# rls_slide_expand_01.net
KiCad netlist of a schematic drawn in EAGLE
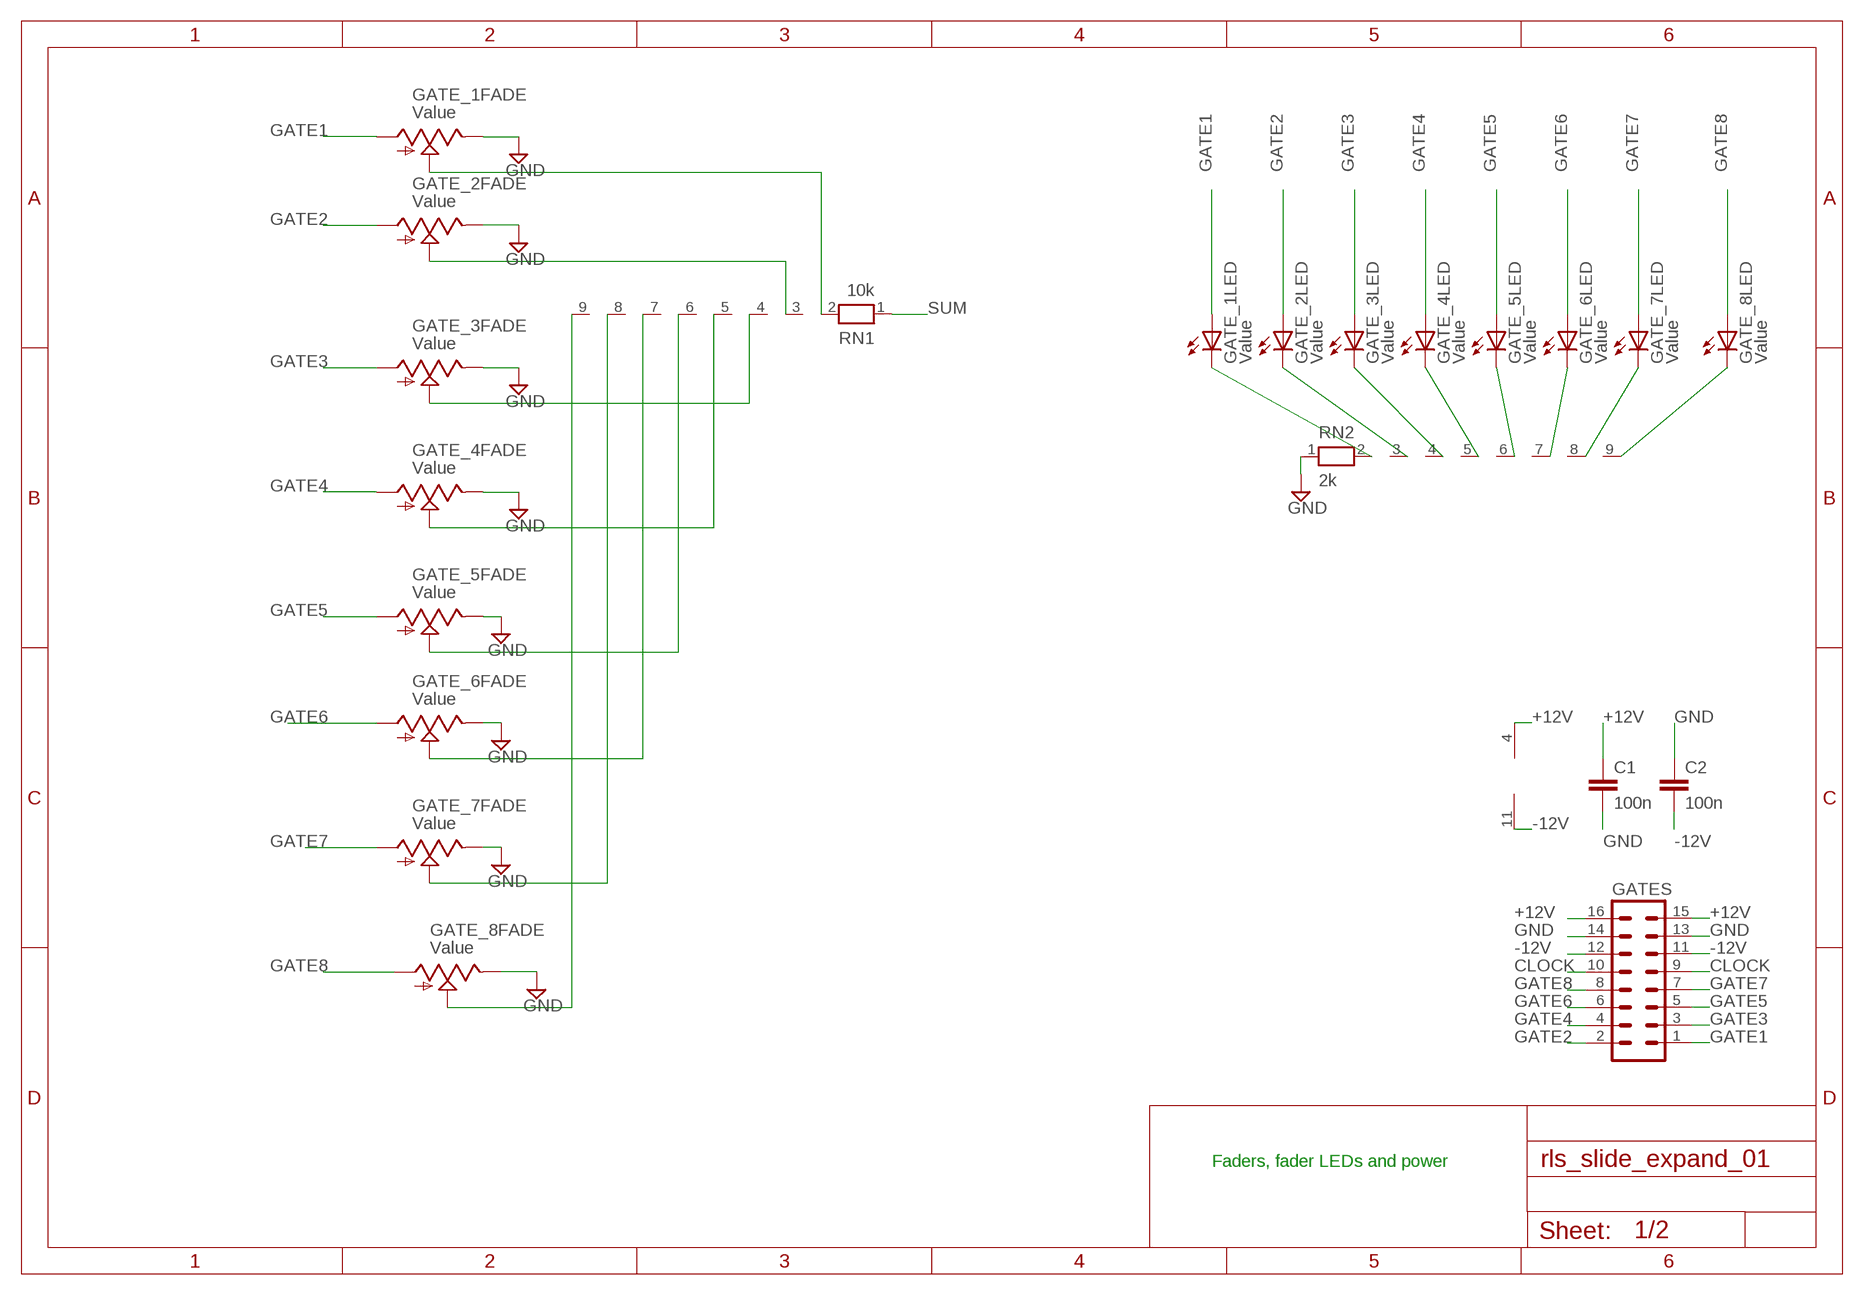
[diagram p0: schematic, sheet 1]
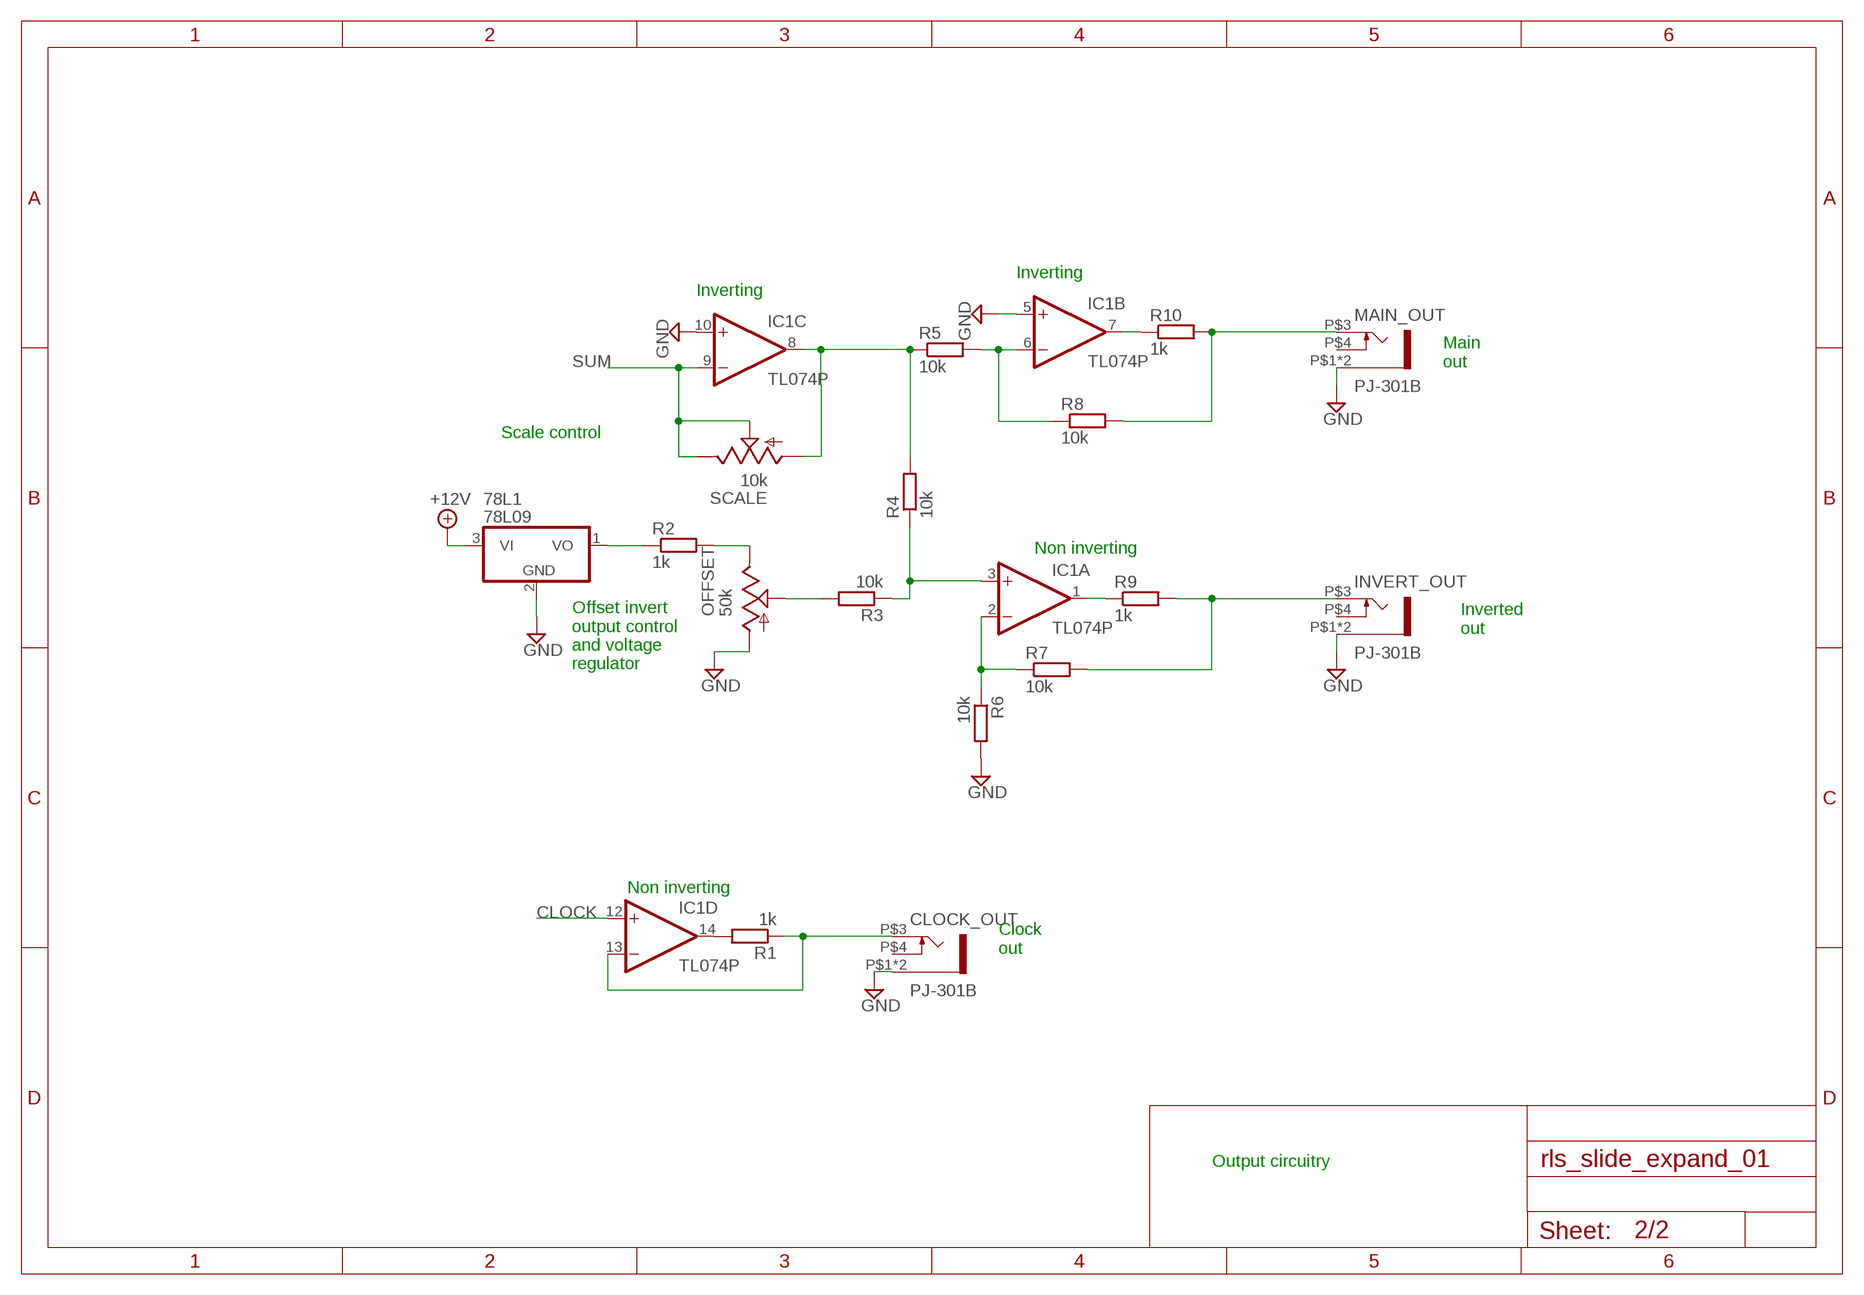
[diagram p1: schematic, sheet 2]

(export (version "E")
  (design (tool "Eeschema 10.0.6"))
  (components
    (comp (ref "78L1")
      (value "78L09")
      (footprint "eagle-import:TO92")
      (libsource (lib "eagle-import") (part "78L08"))
    )
    (comp (ref "CLOCK_OUT")
      (value "PJ-301B")
      (footprint "eagle-import:PJ-301B")
      (libsource (lib "eagle-import") (part "PJ-301B"))
    )
    (comp (ref "IC1")
      (value "TL074P")
      (footprint "eagle-import:DIL14")
      (libsource (lib "eagle-import") (part "TL074P"))
    )
    (comp (ref "INVERT_OUT")
      (value "PJ-301B")
      (footprint "eagle-import:PJ-301B")
      (libsource (lib "eagle-import") (part "PJ-301B"))
    )
    (comp (ref "MAIN_OUT")
      (value "PJ-301B")
      (footprint "eagle-import:PJ-301B")
      (libsource (lib "eagle-import") (part "PJ-301B"))
    )
    (comp (ref "OFFSET")
      (value "50k")
      (footprint "eagle-import:EVUF")
      (libsource (lib "eagle-import") (part "ALPHA-9MMAF2"))
    )
    (comp (ref "R1")
      (value "1k")
      (footprint "eagle-import:0207_10")
      (libsource (lib "eagle-import") (part "R-EU_0207/10"))
    )
    (comp (ref "R2")
      (value "1k")
      (footprint "eagle-import:0207_10")
      (libsource (lib "eagle-import") (part "R-EU_0207/10"))
    )
    (comp (ref "R3")
      (value "10k")
      (footprint "eagle-import:0207_10")
      (libsource (lib "eagle-import") (part "R-EU_0207/10"))
    )
    (comp (ref "R4")
      (value "10k")
      (footprint "eagle-import:0207_10")
      (libsource (lib "eagle-import") (part "R-EU_0207/10"))
    )
    (comp (ref "R5")
      (value "10k")
      (footprint "eagle-import:0207_10")
      (libsource (lib "eagle-import") (part "R-EU_0207/10"))
    )
    (comp (ref "R6")
      (value "10k")
      (footprint "eagle-import:0207_10")
      (libsource (lib "eagle-import") (part "R-EU_0207/10"))
    )
    (comp (ref "R7")
      (value "10k")
      (footprint "eagle-import:0207_10")
      (libsource (lib "eagle-import") (part "R-EU_0207/10"))
    )
    (comp (ref "R8")
      (value "10k")
      (footprint "eagle-import:0207_10")
      (libsource (lib "eagle-import") (part "R-EU_0207/10"))
    )
    (comp (ref "R9")
      (value "1k")
      (footprint "eagle-import:0207_10")
      (libsource (lib "eagle-import") (part "R-EU_0207/10"))
    )
    (comp (ref "R10")
      (value "1k")
      (footprint "eagle-import:0207_10")
      (libsource (lib "eagle-import") (part "R-EU_0207/10"))
    )
    (comp (ref "SCALE")
      (value "10k")
      (footprint "eagle-import:EVUF")
      (libsource (lib "eagle-import") (part "ALPHA-9MMAF2"))
    )
    (comp (ref "C1")
      (value "100n")
      (footprint "eagle-import:C050-024X044")
      (libsource (lib "eagle-import") (part "C-EU050-024X044"))
    )
    (comp (ref "C2")
      (value "100n")
      (footprint "eagle-import:C050-024X044")
      (libsource (lib "eagle-import") (part "C-EU050-024X044"))
    )
    (comp (ref "GATES")
      (value "MA08-2")
      (footprint "eagle-import:MA08-2")
      (libsource (lib "eagle-import") (part "MA08-2"))
    )
    (comp (ref "GATE_1")
      (value "Value")
      (footprint "eagle-import:ALPHA_ILL_FADER_20MM")
      (libsource (lib "eagle-import") (part "ALPHA_20MM_ILLUM_FADER"))
    )
    (comp (ref "GATE_2")
      (value "Value")
      (footprint "eagle-import:ALPHA_ILL_FADER_20MM")
      (libsource (lib "eagle-import") (part "ALPHA_20MM_ILLUM_FADER"))
    )
    (comp (ref "GATE_3")
      (value "Value")
      (footprint "eagle-import:ALPHA_ILL_FADER_20MM")
      (libsource (lib "eagle-import") (part "ALPHA_20MM_ILLUM_FADER"))
    )
    (comp (ref "GATE_4")
      (value "Value")
      (footprint "eagle-import:ALPHA_ILL_FADER_20MM")
      (libsource (lib "eagle-import") (part "ALPHA_20MM_ILLUM_FADER"))
    )
    (comp (ref "GATE_5")
      (value "Value")
      (footprint "eagle-import:ALPHA_ILL_FADER_20MM")
      (libsource (lib "eagle-import") (part "ALPHA_20MM_ILLUM_FADER"))
    )
    (comp (ref "GATE_6")
      (value "Value")
      (footprint "eagle-import:ALPHA_ILL_FADER_20MM")
      (libsource (lib "eagle-import") (part "ALPHA_20MM_ILLUM_FADER"))
    )
    (comp (ref "GATE_7")
      (value "Value")
      (footprint "eagle-import:ALPHA_ILL_FADER_20MM")
      (libsource (lib "eagle-import") (part "ALPHA_20MM_ILLUM_FADER"))
    )
    (comp (ref "GATE_8")
      (value "Value")
      (footprint "eagle-import:ALPHA_ILL_FADER_20MM")
      (libsource (lib "eagle-import") (part "ALPHA_20MM_ILLUM_FADER"))
    )
    (comp (ref "RN1")
      (value "10k")
      (footprint "eagle-import:RN-9")
      (libsource (lib "eagle-import") (part "RN08"))
    )
    (comp (ref "RN2")
      (value "2k")
      (footprint "eagle-import:RN-9")
      (libsource (lib "eagle-import") (part "RN08"))
    )
  )
  (nets
    (net (code "1") (name "+12V") (class "Default")
      (node (ref "78L1") (pin "3") (pinfunction "VI_3") (pintype "input"))
      (node (ref "C1") (pin "1") (pinfunction "1_1") (pintype "passive"))
      (node (ref "GATES") (pin "15") (pinfunction "15_15") (pintype "passive"))
      (node (ref "GATES") (pin "16") (pinfunction "16_16") (pintype "passive"))
      (node (ref "IC1") (pin "4") (pinfunction "V+_4") (pintype "power_in"))
    )
    (net (code "2") (name "-12V") (class "Default")
      (node (ref "C2") (pin "2") (pinfunction "2_2") (pintype "passive"))
      (node (ref "GATES") (pin "11") (pinfunction "11_11") (pintype "passive"))
      (node (ref "GATES") (pin "12") (pinfunction "12_12") (pintype "passive"))
      (node (ref "IC1") (pin "11") (pinfunction "V-_11") (pintype "power_in"))
    )
    (net (code "3") (name "CLOCK") (class "Default")
      (node (ref "GATES") (pin "10") (pinfunction "10_10") (pintype "passive"))
      (node (ref "GATES") (pin "9") (pinfunction "9_9") (pintype "passive"))
      (node (ref "IC1") (pin "12") (pinfunction "+IN_12") (pintype "input"))
    )
    (net (code "4") (name "GATE1") (class "Default")
      (node (ref "GATES") (pin "1") (pinfunction "1_1") (pintype "passive"))
      (node (ref "GATE_1") (pin "3") (pinfunction "A_3") (pintype "passive"))
      (node (ref "GATE_1") (pin "B") (pinfunction "A_B") (pintype "passive"))
    )
    (net (code "5") (name "GATE2") (class "Default")
      (node (ref "GATES") (pin "2") (pinfunction "2_2") (pintype "passive"))
      (node (ref "GATE_2") (pin "3") (pinfunction "A_3") (pintype "passive"))
      (node (ref "GATE_2") (pin "B") (pinfunction "A_B") (pintype "passive"))
    )
    (net (code "6") (name "GATE3") (class "Default")
      (node (ref "GATES") (pin "3") (pinfunction "3_3") (pintype "passive"))
      (node (ref "GATE_3") (pin "3") (pinfunction "A_3") (pintype "passive"))
      (node (ref "GATE_3") (pin "B") (pinfunction "A_B") (pintype "passive"))
    )
    (net (code "7") (name "GATE4") (class "Default")
      (node (ref "GATES") (pin "4") (pinfunction "4_4") (pintype "passive"))
      (node (ref "GATE_4") (pin "3") (pinfunction "A_3") (pintype "passive"))
      (node (ref "GATE_4") (pin "B") (pinfunction "A_B") (pintype "passive"))
    )
    (net (code "8") (name "GATE5") (class "Default")
      (node (ref "GATES") (pin "5") (pinfunction "5_5") (pintype "passive"))
      (node (ref "GATE_5") (pin "3") (pinfunction "A_3") (pintype "passive"))
      (node (ref "GATE_5") (pin "B") (pinfunction "A_B") (pintype "passive"))
    )
    (net (code "9") (name "GATE6") (class "Default")
      (node (ref "GATES") (pin "6") (pinfunction "6_6") (pintype "passive"))
      (node (ref "GATE_6") (pin "3") (pinfunction "A_3") (pintype "passive"))
      (node (ref "GATE_6") (pin "B") (pinfunction "A_B") (pintype "passive"))
    )
    (net (code "10") (name "GATE7") (class "Default")
      (node (ref "GATES") (pin "7") (pinfunction "7_7") (pintype "passive"))
      (node (ref "GATE_7") (pin "3") (pinfunction "A_3") (pintype "passive"))
      (node (ref "GATE_7") (pin "B") (pinfunction "A_B") (pintype "passive"))
    )
    (net (code "11") (name "GATE8") (class "Default")
      (node (ref "GATES") (pin "8") (pinfunction "8_8") (pintype "passive"))
      (node (ref "GATE_8") (pin "3") (pinfunction "A_3") (pintype "passive"))
      (node (ref "GATE_8") (pin "B") (pinfunction "A_B") (pintype "passive"))
    )
    (net (code "12") (name "GND") (class "Default")
      (node (ref "78L1") (pin "2") (pinfunction "GND_2") (pintype "passive"))
      (node (ref "C1") (pin "2") (pinfunction "2_2") (pintype "passive"))
      (node (ref "C2") (pin "1") (pinfunction "1_1") (pintype "passive"))
      (node (ref "CLOCK_OUT") (pin "P$1") (pinfunction "5_P$1") (pintype "passive"))
      (node (ref "CLOCK_OUT") (pin "P$2") (pinfunction "5_P$2") (pintype "passive"))
      (node (ref "GATES") (pin "13") (pinfunction "13_13") (pintype "passive"))
      (node (ref "GATES") (pin "14") (pinfunction "14_14") (pintype "passive"))
      (node (ref "GATE_1") (pin "1") (pinfunction "E_1") (pintype "passive"))
      (node (ref "GATE_2") (pin "1") (pinfunction "E_1") (pintype "passive"))
      (node (ref "GATE_3") (pin "1") (pinfunction "E_1") (pintype "passive"))
      (node (ref "GATE_4") (pin "1") (pinfunction "E_1") (pintype "passive"))
      (node (ref "GATE_5") (pin "1") (pinfunction "E_1") (pintype "passive"))
      (node (ref "GATE_6") (pin "1") (pinfunction "E_1") (pintype "passive"))
      (node (ref "GATE_7") (pin "1") (pinfunction "E_1") (pintype "passive"))
      (node (ref "GATE_8") (pin "1") (pinfunction "E_1") (pintype "passive"))
      (node (ref "IC1") (pin "10") (pinfunction "+IN_10") (pintype "input"))
      (node (ref "IC1") (pin "5") (pinfunction "+IN_5") (pintype "input"))
      (node (ref "INVERT_OUT") (pin "P$1") (pinfunction "5_P$1") (pintype "passive"))
      (node (ref "INVERT_OUT") (pin "P$2") (pinfunction "5_P$2") (pintype "passive"))
      (node (ref "MAIN_OUT") (pin "P$1") (pinfunction "5_P$1") (pintype "passive"))
      (node (ref "MAIN_OUT") (pin "P$2") (pinfunction "5_P$2") (pintype "passive"))
      (node (ref "OFFSET") (pin "1") (pinfunction "A_1") (pintype "passive"))
      (node (ref "R6") (pin "2") (pinfunction "2_2") (pintype "passive"))
      (node (ref "RN2") (pin "1") (pinfunction "1_1") (pintype "passive"))
    )
    (net (code "13") (name "Net-(78L1-VO)") (class "Default")
      (node (ref "78L1") (pin "1") (pinfunction "VO_1") (pintype "passive"))
      (node (ref "R2") (pin "1") (pinfunction "1_1") (pintype "passive"))
    )
    (net (code "14") (name "Net-(CLOCK_OUT-3)") (class "Default")
      (node (ref "CLOCK_OUT") (pin "P$3") (pinfunction "3_P$3") (pintype "passive"))
      (node (ref "IC1") (pin "13") (pinfunction "-IN_13") (pintype "input"))
      (node (ref "R1") (pin "1") (pinfunction "1_1") (pintype "passive"))
    )
    (net (code "15") (name "Net-(GATE_1A-S)") (class "Default")
      (node (ref "GATE_1") (pin "2") (pinfunction "S_2") (pintype "passive"))
      (node (ref "RN1") (pin "2") (pinfunction "2_2") (pintype "passive"))
    )
    (net (code "16") (name "Net-(GATE_1B-C)") (class "Default")
      (node (ref "GATE_1") (pin "E") (pinfunction "C_E") (pintype "passive"))
      (node (ref "RN2") (pin "2") (pinfunction "2_2") (pintype "passive"))
    )
    (net (code "17") (name "Net-(GATE_2A-S)") (class "Default")
      (node (ref "GATE_2") (pin "2") (pinfunction "S_2") (pintype "passive"))
      (node (ref "RN1") (pin "3") (pinfunction "3_3") (pintype "passive"))
    )
    (net (code "18") (name "Net-(GATE_2B-C)") (class "Default")
      (node (ref "GATE_2") (pin "E") (pinfunction "C_E") (pintype "passive"))
      (node (ref "RN2") (pin "3") (pinfunction "3_3") (pintype "passive"))
    )
    (net (code "19") (name "Net-(GATE_3A-S)") (class "Default")
      (node (ref "GATE_3") (pin "2") (pinfunction "S_2") (pintype "passive"))
      (node (ref "RN1") (pin "4") (pinfunction "4_4") (pintype "passive"))
    )
    (net (code "20") (name "Net-(GATE_3B-C)") (class "Default")
      (node (ref "GATE_3") (pin "E") (pinfunction "C_E") (pintype "passive"))
      (node (ref "RN2") (pin "4") (pinfunction "4_4") (pintype "passive"))
    )
    (net (code "21") (name "Net-(GATE_4A-S)") (class "Default")
      (node (ref "GATE_4") (pin "2") (pinfunction "S_2") (pintype "passive"))
      (node (ref "RN1") (pin "5") (pinfunction "5_5") (pintype "passive"))
    )
    (net (code "22") (name "Net-(GATE_4B-C)") (class "Default")
      (node (ref "GATE_4") (pin "E") (pinfunction "C_E") (pintype "passive"))
      (node (ref "RN2") (pin "5") (pinfunction "5_5") (pintype "passive"))
    )
    (net (code "23") (name "Net-(GATE_5A-S)") (class "Default")
      (node (ref "GATE_5") (pin "2") (pinfunction "S_2") (pintype "passive"))
      (node (ref "RN1") (pin "6") (pinfunction "6_6") (pintype "passive"))
    )
    (net (code "24") (name "Net-(GATE_5B-C)") (class "Default")
      (node (ref "GATE_5") (pin "E") (pinfunction "C_E") (pintype "passive"))
      (node (ref "RN2") (pin "6") (pinfunction "6_6") (pintype "passive"))
    )
    (net (code "25") (name "Net-(GATE_6A-S)") (class "Default")
      (node (ref "GATE_6") (pin "2") (pinfunction "S_2") (pintype "passive"))
      (node (ref "RN1") (pin "7") (pinfunction "7_7") (pintype "passive"))
    )
    (net (code "26") (name "Net-(GATE_6B-C)") (class "Default")
      (node (ref "GATE_6") (pin "E") (pinfunction "C_E") (pintype "passive"))
      (node (ref "RN2") (pin "7") (pinfunction "7_7") (pintype "passive"))
    )
    (net (code "27") (name "Net-(GATE_7A-S)") (class "Default")
      (node (ref "GATE_7") (pin "2") (pinfunction "S_2") (pintype "passive"))
      (node (ref "RN1") (pin "8") (pinfunction "8_8") (pintype "passive"))
    )
    (net (code "28") (name "Net-(GATE_7B-C)") (class "Default")
      (node (ref "GATE_7") (pin "E") (pinfunction "C_E") (pintype "passive"))
      (node (ref "RN2") (pin "8") (pinfunction "8_8") (pintype "passive"))
    )
    (net (code "29") (name "Net-(GATE_8A-S)") (class "Default")
      (node (ref "GATE_8") (pin "2") (pinfunction "S_2") (pintype "passive"))
      (node (ref "RN1") (pin "9") (pinfunction "9_9") (pintype "passive"))
    )
    (net (code "30") (name "Net-(GATE_8B-C)") (class "Default")
      (node (ref "GATE_8") (pin "E") (pinfunction "C_E") (pintype "passive"))
      (node (ref "RN2") (pin "9") (pinfunction "9_9") (pintype "passive"))
    )
    (net (code "31") (name "Net-(IC1A-+IN)") (class "Default")
      (node (ref "IC1") (pin "3") (pinfunction "+IN_3") (pintype "input"))
      (node (ref "R3") (pin "1") (pinfunction "1_1") (pintype "passive"))
      (node (ref "R4") (pin "1") (pinfunction "1_1") (pintype "passive"))
    )
    (net (code "32") (name "Net-(IC1A--IN)") (class "Default")
      (node (ref "IC1") (pin "2") (pinfunction "-IN_2") (pintype "input"))
      (node (ref "R6") (pin "1") (pinfunction "1_1") (pintype "passive"))
      (node (ref "R7") (pin "1") (pinfunction "1_1") (pintype "passive"))
    )
    (net (code "33") (name "Net-(IC1A-OUT)") (class "Default")
      (node (ref "IC1") (pin "1") (pinfunction "OUT_1") (pintype "output"))
      (node (ref "R9") (pin "1") (pinfunction "1_1") (pintype "passive"))
    )
    (net (code "34") (name "Net-(IC1B--IN)") (class "Default")
      (node (ref "IC1") (pin "6") (pinfunction "-IN_6") (pintype "input"))
      (node (ref "R5") (pin "2") (pinfunction "2_2") (pintype "passive"))
      (node (ref "R8") (pin "1") (pinfunction "1_1") (pintype "passive"))
    )
    (net (code "35") (name "Net-(IC1B-OUT)") (class "Default")
      (node (ref "IC1") (pin "7") (pinfunction "OUT_7") (pintype "output"))
      (node (ref "R10") (pin "1") (pinfunction "1_1") (pintype "passive"))
    )
    (net (code "36") (name "Net-(IC1C-OUT)") (class "Default")
      (node (ref "IC1") (pin "8") (pinfunction "OUT_8") (pintype "output"))
      (node (ref "R4") (pin "2") (pinfunction "2_2") (pintype "passive"))
      (node (ref "R5") (pin "1") (pinfunction "1_1") (pintype "passive"))
      (node (ref "SCALE") (pin "1") (pinfunction "A_1") (pintype "passive"))
    )
    (net (code "37") (name "Net-(IC1D-OUT)") (class "Default")
      (node (ref "IC1") (pin "14") (pinfunction "OUT_14") (pintype "output"))
      (node (ref "R1") (pin "2") (pinfunction "2_2") (pintype "passive"))
    )
    (net (code "38") (name "Net-(INVERT_OUT-3)") (class "Default")
      (node (ref "INVERT_OUT") (pin "P$3") (pinfunction "3_P$3") (pintype "passive"))
      (node (ref "R7") (pin "2") (pinfunction "2_2") (pintype "passive"))
      (node (ref "R9") (pin "2") (pinfunction "2_2") (pintype "passive"))
    )
    (net (code "39") (name "Net-(MAIN_OUT-3)") (class "Default")
      (node (ref "MAIN_OUT") (pin "P$3") (pinfunction "3_P$3") (pintype "passive"))
      (node (ref "R10") (pin "2") (pinfunction "2_2") (pintype "passive"))
      (node (ref "R8") (pin "2") (pinfunction "2_2") (pintype "passive"))
    )
    (net (code "40") (name "Net-(OFFSET-E)") (class "Default")
      (node (ref "OFFSET") (pin "3") (pinfunction "E_3") (pintype "passive"))
      (node (ref "R2") (pin "2") (pinfunction "2_2") (pintype "passive"))
    )
    (net (code "41") (name "Net-(OFFSET-S)") (class "Default")
      (node (ref "OFFSET") (pin "2") (pinfunction "S_2") (pintype "passive"))
      (node (ref "R3") (pin "2") (pinfunction "2_2") (pintype "passive"))
    )
    (net (code "42") (name "SUM") (class "Default")
      (node (ref "IC1") (pin "9") (pinfunction "-IN_9") (pintype "input"))
      (node (ref "RN1") (pin "1") (pinfunction "1_1") (pintype "passive"))
      (node (ref "SCALE") (pin "2") (pinfunction "S_2") (pintype "passive"))
      (node (ref "SCALE") (pin "3") (pinfunction "E_3") (pintype "passive"))
    )
    (net (code "43") (name "unconnected-(CLOCK_OUT-4-PadP$4)") (class "Default")
      (node (ref "CLOCK_OUT") (pin "P$4") (pinfunction "4_P$4") (pintype "passive"))
    )
    (net (code "44") (name "unconnected-(INVERT_OUT-4-PadP$4)") (class "Default")
      (node (ref "INVERT_OUT") (pin "P$4") (pinfunction "4_P$4") (pintype "passive"))
    )
    (net (code "45") (name "unconnected-(MAIN_OUT-4-PadP$4)") (class "Default")
      (node (ref "MAIN_OUT") (pin "P$4") (pinfunction "4_P$4") (pintype "passive"))
    )
  )
)
